# main.net
KiCad netlist of a schematic drawn in EAGLE
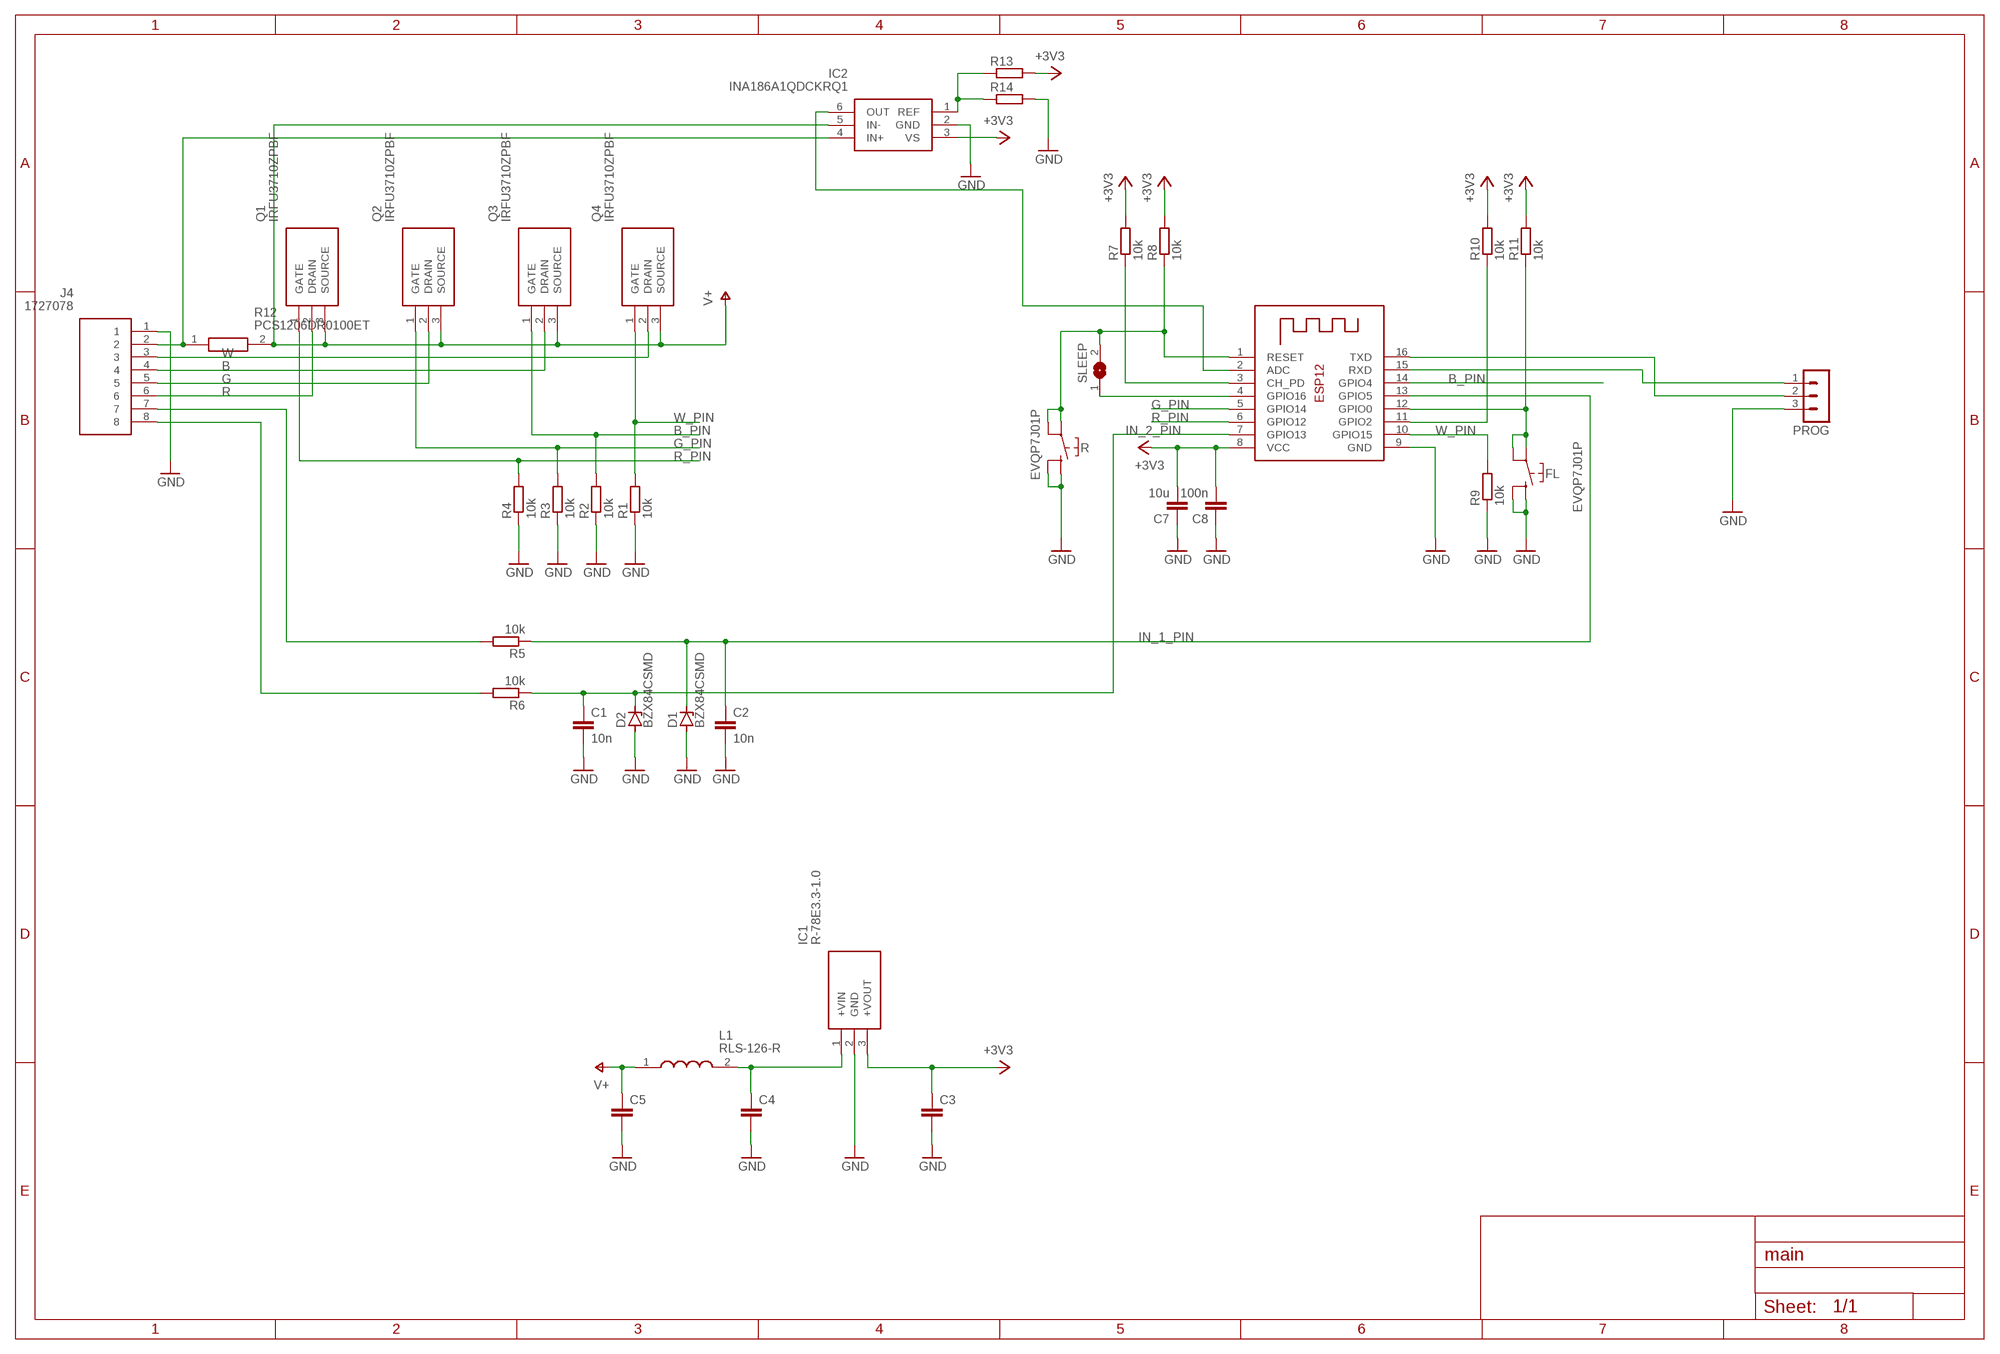
[diagram p0: schematic, sheet 1]

(export (version "E")
  (design (tool "Eeschema 10.0.6"))
  (components
    (comp (ref "C1")
      (value "10n")
      (footprint "eagle-import:C0603")
      (libsource (lib "eagle-import") (part "C-EUC0603"))
    )
    (comp (ref "C2")
      (value "10n")
      (footprint "eagle-import:C0603")
      (libsource (lib "eagle-import") (part "C-EUC0603"))
    )
    (comp (ref "C3")
      (value "C-EUC0603")
      (footprint "eagle-import:C0603")
      (libsource (lib "eagle-import") (part "C-EUC0603"))
    )
    (comp (ref "C4")
      (value "C-EUC1206")
      (footprint "eagle-import:C1206")
      (libsource (lib "eagle-import") (part "C-EUC1206"))
    )
    (comp (ref "C5")
      (value "C-EUC1206")
      (footprint "eagle-import:C1206")
      (libsource (lib "eagle-import") (part "C-EUC1206"))
    )
    (comp (ref "C7")
      (value "10u")
      (footprint "eagle-import:C0603")
      (libsource (lib "eagle-import") (part "C-EUC0603"))
    )
    (comp (ref "C8")
      (value "100n")
      (footprint "eagle-import:C0603")
      (libsource (lib "eagle-import") (part "C-EUC0603"))
    )
    (comp (ref "D1")
      (value "BZX84CSMD")
      (footprint "eagle-import:TO236")
      (libsource (lib "eagle-import") (part "BZX84CSMD"))
    )
    (comp (ref "D2")
      (value "BZX84CSMD")
      (footprint "eagle-import:TO236")
      (libsource (lib "eagle-import") (part "BZX84CSMD"))
    )
    (comp (ref "FL")
      (value "EVQP7J01P")
      (footprint "eagle-import:EVQP7J01P")
      (libsource (lib "eagle-import") (part "EVQP7J01P"))
    )
    (comp (ref "IC1")
      (value "R-78E3.3-1.0")
      (footprint "eagle-import:R78E3310")
      (fields (field (name "MOUSER_PART_NUMBER") "919-R-78E3.3-1.0"))
      (libsource (lib "eagle-import") (part "R-78E3.3-1.0"))
    )
    (comp (ref "IC2")
      (value "INA186A1QDCKRQ1")
      (footprint "eagle-import:SOP65P210X110-6N")
      (fields (field (name "MOUSER_PART_NUMBER") "595-INA186A1QDCKRQ1"))
      (libsource (lib "eagle-import") (part "INA186A1QDCKRQ1"))
    )
    (comp (ref "J4")
      (value "1727078")
      (footprint "eagle-import:SHDR8W90P0X381_1X8_3047X730X86")
      (fields (field (name "MOUSER_PART_NUMBER") "651-1727078") (field (name "RS_PART_NUMBER") "2204399"))
      (libsource (lib "eagle-import") (part "1727078"))
    )
    (comp (ref "L1")
      (value "RLS-126-R")
      (footprint "eagle-import:RLS126R")
      (fields (field (name "MOUSER_PART_NUMBER") "919-RLS-126-R"))
      (libsource (lib "eagle-import") (part "RLS-126-R"))
    )
    (comp (ref "PROG")
      (value "MA03-1")
      (footprint "eagle-import:MA03-1")
      (libsource (lib "eagle-import") (part "MA03-1"))
    )
    (comp (ref "Q1")
      (value "IRFU3710ZPBF")
      (footprint "eagle-import:TO229P239X654X978-3P")
      (fields (field (name "MOUSER_PART_NUMBER") "942-IRFU3710ZPBF"))
      (libsource (lib "eagle-import") (part "IRFU3710ZPBF"))
    )
    (comp (ref "Q2")
      (value "IRFU3710ZPBF")
      (footprint "eagle-import:TO229P239X654X978-3P")
      (fields (field (name "MOUSER_PART_NUMBER") "942-IRFU3710ZPBF"))
      (libsource (lib "eagle-import") (part "IRFU3710ZPBF"))
    )
    (comp (ref "Q3")
      (value "IRFU3710ZPBF")
      (footprint "eagle-import:TO229P239X654X978-3P")
      (fields (field (name "MOUSER_PART_NUMBER") "942-IRFU3710ZPBF"))
      (libsource (lib "eagle-import") (part "IRFU3710ZPBF"))
    )
    (comp (ref "Q4")
      (value "IRFU3710ZPBF")
      (footprint "eagle-import:TO229P239X654X978-3P")
      (fields (field (name "MOUSER_PART_NUMBER") "942-IRFU3710ZPBF"))
      (libsource (lib "eagle-import") (part "IRFU3710ZPBF"))
    )
    (comp (ref "R")
      (value "EVQP7J01P")
      (footprint "eagle-import:EVQP7J01P")
      (libsource (lib "eagle-import") (part "EVQP7J01P"))
    )
    (comp (ref "R1")
      (value "10k")
      (footprint "eagle-import:R0603")
      (libsource (lib "eagle-import") (part "R-EU_R0603"))
    )
    (comp (ref "R2")
      (value "10k")
      (footprint "eagle-import:R0603")
      (libsource (lib "eagle-import") (part "R-EU_R0603"))
    )
    (comp (ref "R3")
      (value "10k")
      (footprint "eagle-import:R0603")
      (libsource (lib "eagle-import") (part "R-EU_R0603"))
    )
    (comp (ref "R4")
      (value "10k")
      (footprint "eagle-import:R0603")
      (libsource (lib "eagle-import") (part "R-EU_R0603"))
    )
    (comp (ref "R5")
      (value "10k")
      (footprint "eagle-import:R0603")
      (libsource (lib "eagle-import") (part "R-EU_R0603"))
    )
    (comp (ref "R6")
      (value "10k")
      (footprint "eagle-import:R0603")
      (libsource (lib "eagle-import") (part "R-EU_R0603"))
    )
    (comp (ref "R7")
      (value "10k")
      (footprint "eagle-import:R0603")
      (libsource (lib "eagle-import") (part "R-EU_R0603"))
    )
    (comp (ref "R8")
      (value "10k")
      (footprint "eagle-import:R0603")
      (libsource (lib "eagle-import") (part "R-EU_R0603"))
    )
    (comp (ref "R9")
      (value "10k")
      (footprint "eagle-import:R0603")
      (libsource (lib "eagle-import") (part "R-EU_R0603"))
    )
    (comp (ref "R10")
      (value "10k")
      (footprint "eagle-import:R0603")
      (libsource (lib "eagle-import") (part "R-EU_R0603"))
    )
    (comp (ref "R11")
      (value "10k")
      (footprint "eagle-import:R0603")
      (libsource (lib "eagle-import") (part "R-EU_R0603"))
    )
    (comp (ref "R12")
      (value "PCS1206DR0100ET")
      (footprint "eagle-import:RESC3216X68N")
      (fields (field (name "MOUSER_PART_NUMBER") "588-PCS1206DR0100ET"))
      (libsource (lib "eagle-import") (part "PCS1206DR0100ET"))
    )
    (comp (ref "R13")
      (value "R-EU_R0402")
      (footprint "eagle-import:R0402")
      (libsource (lib "eagle-import") (part "R-EU_R0402"))
    )
    (comp (ref "R14")
      (value "R-EU_R0402")
      (footprint "eagle-import:R0402")
      (libsource (lib "eagle-import") (part "R-EU_R0402"))
    )
    (comp (ref "SLEEP")
      (value "SJ")
      (footprint "eagle-import:SJ")
      (libsource (lib "eagle-import") (part "SJ"))
    )
    (comp (ref "X2")
      (value "ESP-12")
      (footprint "eagle-import:ESP-12")
      (libsource (lib "eagle-import") (part "ESP-12"))
    )
  )
  (nets
    (net (code "1") (name "+3V3") (class "Default")
      (node (ref "C3") (pin "1") (pinfunction "1_1") (pintype "passive"))
      (node (ref "C7") (pin "2") (pinfunction "2_2") (pintype "passive"))
      (node (ref "C8") (pin "2") (pinfunction "2_2") (pintype "passive"))
      (node (ref "IC1") (pin "3") (pinfunction "+VOUT_3") (pintype "bidirectional"))
      (node (ref "IC2") (pin "3") (pinfunction "VS_3") (pintype "bidirectional"))
      (node (ref "R10") (pin "2") (pinfunction "2_2") (pintype "passive"))
      (node (ref "R11") (pin "2") (pinfunction "2_2") (pintype "passive"))
      (node (ref "R13") (pin "2") (pinfunction "2_2") (pintype "passive"))
      (node (ref "R7") (pin "2") (pinfunction "2_2") (pintype "passive"))
      (node (ref "R8") (pin "2") (pinfunction "2_2") (pintype "passive"))
      (node (ref "X2") (pin "8") (pinfunction "VCC_8") (pintype "power_in"))
    )
    (net (code "2") (name "/B") (class "Default")
      (node (ref "J4") (pin "4") (pinfunction "4_4") (pintype "bidirectional"))
      (node (ref "Q3") (pin "2") (pinfunction "DRAIN_2") (pintype "bidirectional"))
    )
    (net (code "3") (name "/B_PIN") (class "Default")
      (node (ref "Q3") (pin "1") (pinfunction "GATE_1") (pintype "bidirectional"))
      (node (ref "R2") (pin "2") (pinfunction "2_2") (pintype "passive"))
      (node (ref "X2") (pin "14") (pinfunction "GPIO4_14") (pintype "bidirectional"))
    )
    (net (code "4") (name "/G") (class "Default")
      (node (ref "J4") (pin "5") (pinfunction "5_5") (pintype "bidirectional"))
      (node (ref "Q2") (pin "2") (pinfunction "DRAIN_2") (pintype "bidirectional"))
    )
    (net (code "5") (name "/G_PIN") (class "Default")
      (node (ref "Q2") (pin "1") (pinfunction "GATE_1") (pintype "bidirectional"))
      (node (ref "R3") (pin "2") (pinfunction "2_2") (pintype "passive"))
      (node (ref "X2") (pin "5") (pinfunction "GPIO14_5") (pintype "bidirectional"))
    )
    (net (code "6") (name "/IN_1_PIN") (class "Default")
      (node (ref "C2") (pin "1") (pinfunction "1_1") (pintype "passive"))
      (node (ref "D1") (pin "C") (pinfunction "C_C") (pintype "passive"))
      (node (ref "R5") (pin "1") (pinfunction "1_1") (pintype "passive"))
      (node (ref "X2") (pin "13") (pinfunction "GPIO5_13") (pintype "bidirectional"))
    )
    (net (code "7") (name "/IN_2_PIN") (class "Default")
      (node (ref "C1") (pin "1") (pinfunction "1_1") (pintype "passive"))
      (node (ref "D2") (pin "C") (pinfunction "C_C") (pintype "passive"))
      (node (ref "R6") (pin "1") (pinfunction "1_1") (pintype "passive"))
      (node (ref "X2") (pin "7") (pinfunction "GPIO13_7") (pintype "bidirectional"))
    )
    (net (code "8") (name "/R") (class "Default")
      (node (ref "J4") (pin "6") (pinfunction "6_6") (pintype "bidirectional"))
      (node (ref "Q1") (pin "2") (pinfunction "DRAIN_2") (pintype "bidirectional"))
    )
    (net (code "9") (name "/R_PIN") (class "Default")
      (node (ref "Q1") (pin "1") (pinfunction "GATE_1") (pintype "bidirectional"))
      (node (ref "R4") (pin "2") (pinfunction "2_2") (pintype "passive"))
      (node (ref "X2") (pin "6") (pinfunction "GPIO12_6") (pintype "bidirectional"))
    )
    (net (code "10") (name "/W") (class "Default")
      (node (ref "J4") (pin "3") (pinfunction "3_3") (pintype "bidirectional"))
      (node (ref "Q4") (pin "2") (pinfunction "DRAIN_2") (pintype "bidirectional"))
    )
    (net (code "11") (name "/W_PIN") (class "Default")
      (node (ref "Q4") (pin "1") (pinfunction "GATE_1") (pintype "bidirectional"))
      (node (ref "R1") (pin "2") (pinfunction "2_2") (pintype "passive"))
      (node (ref "R9") (pin "2") (pinfunction "2_2") (pintype "passive"))
      (node (ref "X2") (pin "10") (pinfunction "GPIO15_10") (pintype "bidirectional"))
    )
    (net (code "12") (name "GND") (class "Default")
      (node (ref "C1") (pin "2") (pinfunction "2_2") (pintype "passive"))
      (node (ref "C2") (pin "2") (pinfunction "2_2") (pintype "passive"))
      (node (ref "C3") (pin "2") (pinfunction "2_2") (pintype "passive"))
      (node (ref "C4") (pin "2") (pinfunction "2_2") (pintype "passive"))
      (node (ref "C5") (pin "2") (pinfunction "2_2") (pintype "passive"))
      (node (ref "C7") (pin "1") (pinfunction "1_1") (pintype "passive"))
      (node (ref "C8") (pin "1") (pinfunction "1_1") (pintype "passive"))
      (node (ref "D1") (pin "A") (pinfunction "A_A") (pintype "passive"))
      (node (ref "D2") (pin "A") (pinfunction "A_A") (pintype "passive"))
      (node (ref "FL") (pin "A2") (pinfunction "COM_1_A2") (pintype "bidirectional"))
      (node (ref "FL") (pin "B2") (pinfunction "COM_2_B2") (pintype "bidirectional"))
      (node (ref "IC1") (pin "2") (pinfunction "GND_2") (pintype "bidirectional"))
      (node (ref "IC2") (pin "2") (pinfunction "GND_2") (pintype "bidirectional"))
      (node (ref "J4") (pin "1") (pinfunction "1_1") (pintype "bidirectional"))
      (node (ref "PROG") (pin "3") (pinfunction "3_3") (pintype "passive"))
      (node (ref "R") (pin "A2") (pinfunction "COM_1_A2") (pintype "bidirectional"))
      (node (ref "R") (pin "B2") (pinfunction "COM_2_B2") (pintype "bidirectional"))
      (node (ref "R1") (pin "1") (pinfunction "1_1") (pintype "passive"))
      (node (ref "R14") (pin "2") (pinfunction "2_2") (pintype "passive"))
      (node (ref "R2") (pin "1") (pinfunction "1_1") (pintype "passive"))
      (node (ref "R3") (pin "1") (pinfunction "1_1") (pintype "passive"))
      (node (ref "R4") (pin "1") (pinfunction "1_1") (pintype "passive"))
      (node (ref "R9") (pin "1") (pinfunction "1_1") (pintype "passive"))
      (node (ref "X2") (pin "9") (pinfunction "GND_9") (pintype "power_in"))
    )
    (net (code "13") (name "Net-(FL-NO_1)") (class "Default")
      (node (ref "FL") (pin "A1") (pinfunction "NO_1_A1") (pintype "bidirectional"))
      (node (ref "FL") (pin "B1") (pinfunction "NO_2_B1") (pintype "bidirectional"))
      (node (ref "R11") (pin "1") (pinfunction "1_1") (pintype "passive"))
      (node (ref "X2") (pin "12") (pinfunction "GPIO0_12") (pintype "bidirectional"))
    )
    (net (code "14") (name "Net-(IC1-+VIN)") (class "Default")
      (node (ref "C4") (pin "1") (pinfunction "1_1") (pintype "passive"))
      (node (ref "IC1") (pin "1") (pinfunction "+VIN_1") (pintype "bidirectional"))
      (node (ref "L1") (pin "2") (pinfunction "2_2") (pintype "bidirectional"))
    )
    (net (code "15") (name "Net-(IC2-IN+)") (class "Default")
      (node (ref "IC2") (pin "4") (pinfunction "IN+_4") (pintype "bidirectional"))
      (node (ref "J4") (pin "2") (pinfunction "2_2") (pintype "bidirectional"))
      (node (ref "R12") (pin "1") (pinfunction "1_1") (pintype "bidirectional"))
    )
    (net (code "16") (name "Net-(IC2-OUT)") (class "Default")
      (node (ref "IC2") (pin "6") (pinfunction "OUT_6") (pintype "bidirectional"))
      (node (ref "X2") (pin "2") (pinfunction "ADC_2") (pintype "passive"))
    )
    (net (code "17") (name "Net-(IC2-REF)") (class "Default")
      (node (ref "IC2") (pin "1") (pinfunction "REF_1") (pintype "bidirectional"))
      (node (ref "R13") (pin "1") (pinfunction "1_1") (pintype "passive"))
      (node (ref "R14") (pin "1") (pinfunction "1_1") (pintype "passive"))
    )
    (net (code "18") (name "Net-(J4-Pad7)") (class "Default")
      (node (ref "J4") (pin "7") (pinfunction "7_7") (pintype "bidirectional"))
      (node (ref "R5") (pin "2") (pinfunction "2_2") (pintype "passive"))
    )
    (net (code "19") (name "Net-(J4-Pad8)") (class "Default")
      (node (ref "J4") (pin "8") (pinfunction "8_8") (pintype "bidirectional"))
      (node (ref "R6") (pin "2") (pinfunction "2_2") (pintype "passive"))
    )
    (net (code "20") (name "Net-(R-NO_1)") (class "Default")
      (node (ref "R") (pin "A1") (pinfunction "NO_1_A1") (pintype "bidirectional"))
      (node (ref "R") (pin "B1") (pinfunction "NO_2_B1") (pintype "bidirectional"))
      (node (ref "R8") (pin "1") (pinfunction "1_1") (pintype "passive"))
      (node (ref "SLEEP") (pin "2") (pinfunction "2_2") (pintype "passive"))
      (node (ref "X2") (pin "1") (pinfunction "RESET_1") (pintype "input"))
    )
    (net (code "21") (name "Net-(X2-CH_PD)") (class "Default")
      (node (ref "R7") (pin "1") (pinfunction "1_1") (pintype "passive"))
      (node (ref "X2") (pin "3") (pinfunction "CH_PD_3") (pintype "input"))
    )
    (net (code "22") (name "Net-(X2-GPIO2)") (class "Default")
      (node (ref "R10") (pin "1") (pinfunction "1_1") (pintype "passive"))
      (node (ref "X2") (pin "11") (pinfunction "GPIO2_11") (pintype "bidirectional"))
    )
    (net (code "23") (name "Net-(X2-GPIO16)") (class "Default")
      (node (ref "SLEEP") (pin "1") (pinfunction "1_1") (pintype "passive"))
      (node (ref "X2") (pin "4") (pinfunction "GPIO16_4") (pintype "bidirectional"))
    )
    (net (code "24") (name "Net-(X2-RXD)") (class "Default")
      (node (ref "PROG") (pin "1") (pinfunction "1_1") (pintype "passive"))
      (node (ref "X2") (pin "15") (pinfunction "RXD_15") (pintype "input"))
    )
    (net (code "25") (name "Net-(X2-TXD)") (class "Default")
      (node (ref "PROG") (pin "2") (pinfunction "2_2") (pintype "passive"))
      (node (ref "X2") (pin "16") (pinfunction "TXD_16") (pintype "output"))
    )
    (net (code "26") (name "V+") (class "Default")
      (node (ref "C5") (pin "1") (pinfunction "1_1") (pintype "passive"))
      (node (ref "IC2") (pin "5") (pinfunction "IN-_5") (pintype "bidirectional"))
      (node (ref "L1") (pin "1") (pinfunction "1_1") (pintype "bidirectional"))
      (node (ref "Q1") (pin "3") (pinfunction "SOURCE_3") (pintype "bidirectional"))
      (node (ref "Q2") (pin "3") (pinfunction "SOURCE_3") (pintype "bidirectional"))
      (node (ref "Q3") (pin "3") (pinfunction "SOURCE_3") (pintype "bidirectional"))
      (node (ref "Q4") (pin "3") (pinfunction "SOURCE_3") (pintype "bidirectional"))
      (node (ref "R12") (pin "2") (pinfunction "2_2") (pintype "bidirectional"))
    )
  )
)
